# CW308T_EFR32MG21.net
KiCad netlist of a schematic drawn in Altium Designer
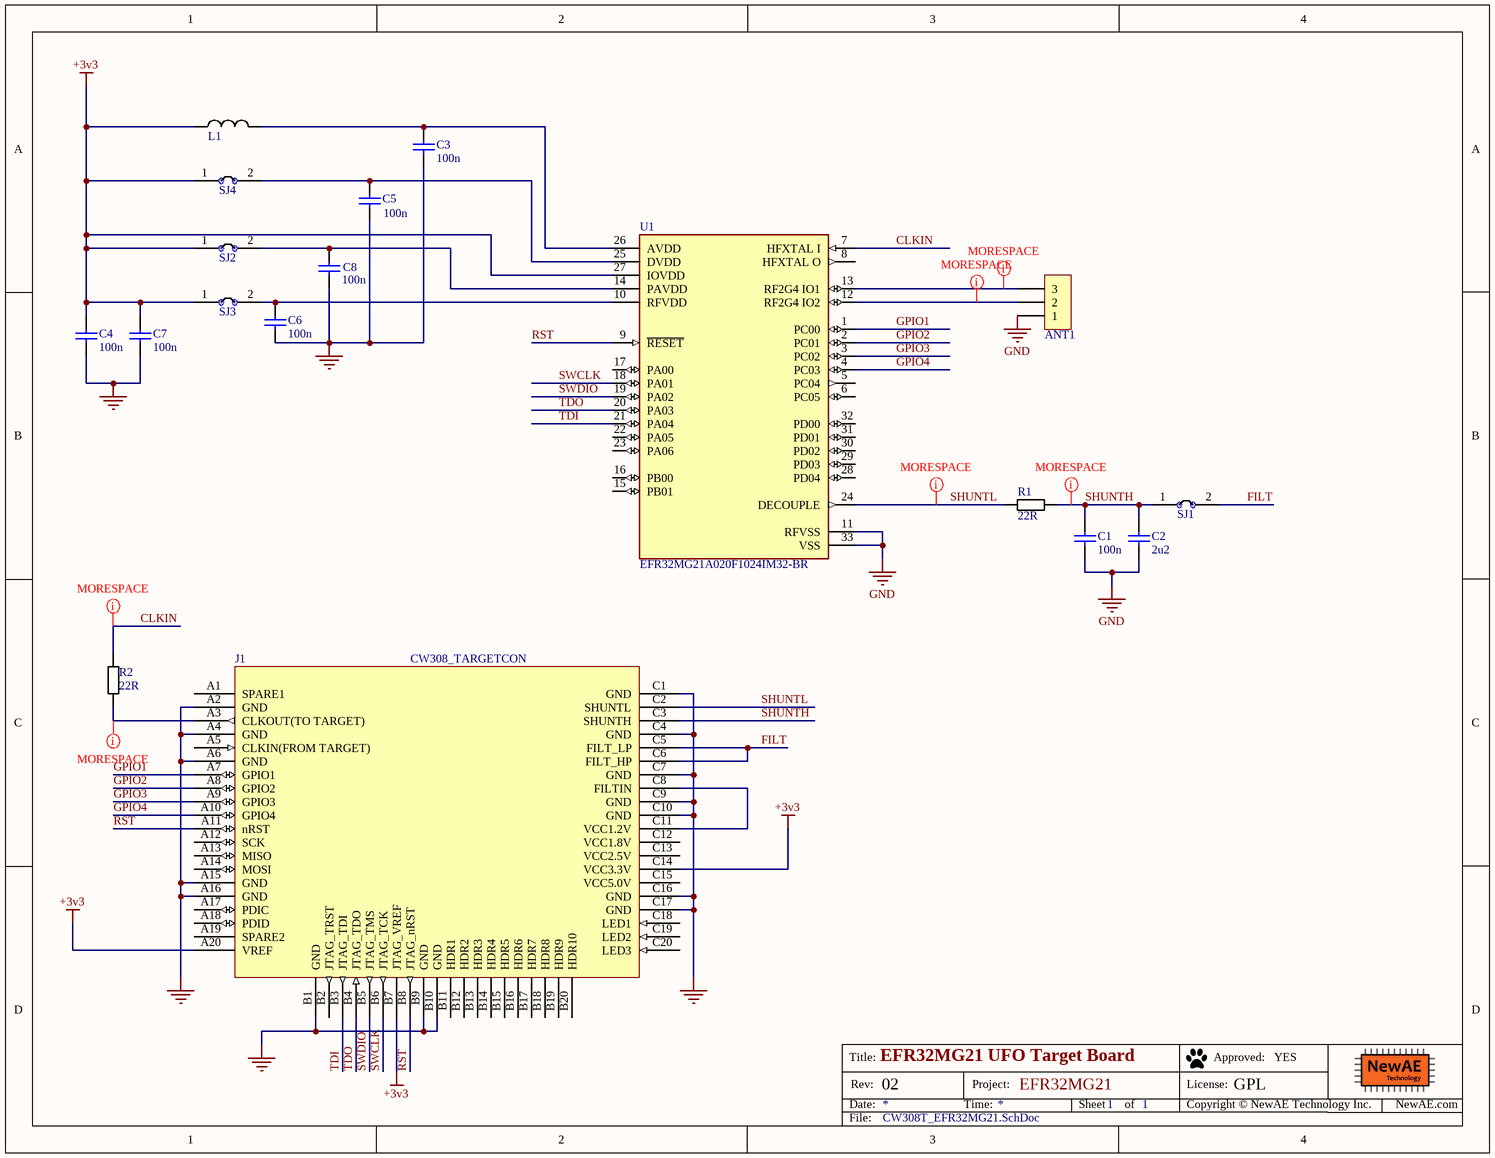
[diagram p0: CW308T_EFR32MG21.SchDoc]

(export (version "E")
  (design (tool "Eeschema 10.0.6"))
  (components
    (comp (ref "ANT1")
      (value "Straight Header Pins")
      (footprint "1x3_Straight_pins")
      (description "1x3 Straight pin header")
      (fields (field (name "PART NUMBER") "HDR_3PIN"))
      (libsource (lib "NewAE_AltiumLib") (part "1x3_Pin_Header"))
    )
    (comp (ref "C1")
      (value "100n")
      (footprint "CAPC0603_M")
      (description "100n, 0603")
      (fields (field (name "PART NUMBER") "CCHIP-100n-0603"))
      (libsource (lib "NewAE_AltiumLib") (part "CAP"))
    )
    (comp (ref "C2")
      (value "2u2")
      (footprint "CAPC0603_M")
      (description "2u2, 0603")
      (fields (field (name "PART NUMBER") "CCHIP-2u2-0603"))
      (libsource (lib "NewAE_AltiumLib") (part "CAP"))
    )
    (comp (ref "C3")
      (value "100n")
      (footprint "CAPC0603_M")
      (description "100n, 0603")
      (fields (field (name "PART NUMBER") "CCHIP-100n-0603"))
      (libsource (lib "NewAE_AltiumLib") (part "CAP"))
    )
    (comp (ref "C4")
      (value "100n")
      (footprint "CAPC0603_M")
      (description "100n, 0603")
      (fields (field (name "PART NUMBER") "CCHIP-100n-0603"))
      (libsource (lib "NewAE_AltiumLib") (part "CAP"))
    )
    (comp (ref "C5")
      (value "100n")
      (footprint "CAPC0603_M")
      (description "100n, 0603")
      (fields (field (name "PART NUMBER") "CCHIP-100n-0603"))
      (libsource (lib "NewAE_AltiumLib") (part "CAP"))
    )
    (comp (ref "C6")
      (value "100n")
      (footprint "CAPC0603_M")
      (description "100n, 0603")
      (fields (field (name "PART NUMBER") "CCHIP-100n-0603"))
      (libsource (lib "NewAE_AltiumLib") (part "CAP"))
    )
    (comp (ref "C7")
      (value "100n")
      (footprint "CAPC0603_M")
      (description "100n, 0603")
      (fields (field (name "PART NUMBER") "CCHIP-100n-0603"))
      (libsource (lib "NewAE_AltiumLib") (part "CAP"))
    )
    (comp (ref "C8")
      (value "100n")
      (footprint "CAPC0603_M")
      (description "100n, 0603")
      (fields (field (name "PART NUMBER") "CCHIP-100n-0603"))
      (libsource (lib "NewAE_AltiumLib") (part "CAP"))
    )
    (comp (ref "J1")
      (value "CW308_TARGETCON")
      (footprint "CW308_TBOARD_CONN")
      (description "CW308 \"Standard\" Target Board Connector")
      (fields (field (name "PART NUMBER") "CW308_TBOARD"))
      (libsource (lib "NewAE_AltiumLib") (part "CW308_TBOARD"))
    )
    (comp (ref "L1")
      (value "1k @ 1Mhz")
      (footprint "IND_0603")
      (description "Ferrite Beads HI CUR CHIP BD 0603 1000OHMS 25%")
      (fields (field (name "PART NUMBER") "FBCHIP-1k-0603"))
      (libsource (lib "NewAE_AltiumLib") (part "IND"))
    )
    (comp (ref "R1")
      (value "22R")
      (footprint "RESC1608X55N")
      (description "22R res, 0603, 1%, 1/10W")
      (fields (field (name "PART NUMBER") "RCHIP-22R-0603") (field (name "TOLERANCE") "1%"))
      (libsource (lib "") (part "RES-EU_1"))
    )
    (comp (ref "R2")
      (value "22R")
      (footprint "RESC1608X55N")
      (description "22R res, 0603, 1%, 1/10W")
      (fields (field (name "PART NUMBER") "RCHIP-22R-0603") (field (name "TOLERANCE") "1%"))
      (libsource (lib "NewAE_AltiumLib") (part "RES-EU"))
    )
    (comp (ref "SJ1")
      (value "NC")
      (footprint "SJ_2S_NC")
      (description "Solder Jumper, NC")
      (fields (field (name "PART NUMBER") "SJ_2S"))
      (libsource (lib "NewAE_AltiumLib") (part "SJ_2S"))
    )
    (comp (ref "SJ2")
      (value "NC")
      (footprint "SJ_2S_NC")
      (description "Solder Jumper, NC")
      (fields (field (name "PART NUMBER") "SJ_2S"))
      (libsource (lib "NewAE_AltiumLib") (part "SJ_2S"))
    )
    (comp (ref "SJ3")
      (value "NC")
      (footprint "SJ_2S_NC")
      (description "Solder Jumper, NC")
      (fields (field (name "PART NUMBER") "SJ_2S"))
      (libsource (lib "NewAE_AltiumLib") (part "SJ_2S"))
    )
    (comp (ref "SJ4")
      (value "NC")
      (footprint "SJ_2S_NC")
      (description "Solder Jumper, NC")
      (fields (field (name "PART NUMBER") "SJ_2S"))
      (libsource (lib "NewAE_AltiumLib") (part "SJ_2S"))
    )
    (comp (ref "U1")
      (value "EFR32MG21A020F1024IM32-BR")
      (footprint "FP-EFR32MG21A020F1024IM32-MFG")
      (description "IC MCU 2.4G 20DB MULTIPROTOCOL")
      (fields
        (field (name "MANUFACTURER") "Silicon Labs")
        (field (name "OCTOPART") "https://octopart.com/efr32mg21a020f1024im32-br-silicon+labs-98975230")
      )
      (libsource (lib "Altium Content Vault") (part "b191411bf8830235ba6647a90e145a1"))
    )
  )
  (nets
    (net (code "1") (name "+3v3") (class "Default")
      (node (ref "C4") (pin "1") (pinfunction "1_1") (pintype "passive"))
      (node (ref "C7") (pin "1") (pinfunction "1_1") (pintype "passive"))
      (node (ref "J1") (pin "A20") (pinfunction "VREF_A20") (pintype "tri_state"))
      (node (ref "J1") (pin "B7") (pinfunction "JTAG_VREF_B7") (pintype "tri_state"))
      (node (ref "J1") (pin "C14") (pinfunction "VCC3.3V_C14") (pintype "power_in"))
      (node (ref "L1") (pin "1") (pinfunction "1_1") (pintype "passive"))
      (node (ref "SJ2") (pin "1") (pinfunction "1_1") (pintype "passive"))
      (node (ref "SJ3") (pin "1") (pinfunction "1_1") (pintype "passive"))
      (node (ref "SJ4") (pin "1") (pinfunction "1_1") (pintype "passive"))
      (node (ref "U1") (pin "27") (pinfunction "IOVDD_27") (pintype "power_in"))
    )
    (net (code "2") (name "/CLKIN") (class "Default")
      (node (ref "R2") (pin "1") (pinfunction "1_1") (pintype "passive"))
      (node (ref "U1") (pin "7") (pinfunction "HFXTAL_I_7") (pintype "input"))
    )
    (net (code "3") (name "/FILT") (class "Default")
      (node (ref "J1") (pin "C5") (pinfunction "FILT_LP_C5") (pintype "passive"))
      (node (ref "J1") (pin "C6") (pinfunction "FILT_HP_C6") (pintype "passive"))
      (node (ref "SJ1") (pin "2") (pinfunction "2_2") (pintype "passive"))
    )
    (net (code "4") (name "/GPIO1") (class "Default")
      (node (ref "J1") (pin "A7") (pinfunction "GPIO1_A7") (pintype "bidirectional"))
      (node (ref "U1") (pin "1") (pinfunction "PC00_1") (pintype "bidirectional"))
    )
    (net (code "5") (name "/GPIO2") (class "Default")
      (node (ref "J1") (pin "A8") (pinfunction "GPIO2_A8") (pintype "bidirectional"))
      (node (ref "U1") (pin "2") (pinfunction "PC01_2") (pintype "bidirectional"))
    )
    (net (code "6") (name "/GPIO3") (class "Default")
      (node (ref "J1") (pin "A9") (pinfunction "GPIO3_A9") (pintype "bidirectional"))
      (node (ref "U1") (pin "3") (pinfunction "PC02_3") (pintype "bidirectional"))
    )
    (net (code "7") (name "/GPIO4") (class "Default")
      (node (ref "J1") (pin "A10") (pinfunction "GPIO4_A10") (pintype "bidirectional"))
      (node (ref "U1") (pin "4") (pinfunction "PC03_4") (pintype "bidirectional"))
    )
    (net (code "8") (name "/RST") (class "Default")
      (node (ref "J1") (pin "A11") (pinfunction "nRST_A11") (pintype "bidirectional"))
      (node (ref "J1") (pin "B8") (pinfunction "JTAG_nRST_B8") (pintype "output"))
      (node (ref "U1") (pin "9") (pinfunction "~{RESET}_9") (pintype "input"))
    )
    (net (code "9") (name "/SHUNTH") (class "Default")
      (node (ref "C1") (pin "1") (pinfunction "1_1") (pintype "passive"))
      (node (ref "C2") (pin "1") (pinfunction "1_1") (pintype "passive"))
      (node (ref "J1") (pin "C3") (pinfunction "SHUNTH_C3") (pintype "passive"))
      (node (ref "R1") (pin "2") (pinfunction "2_2") (pintype "passive"))
      (node (ref "SJ1") (pin "1") (pinfunction "1_1") (pintype "passive"))
    )
    (net (code "10") (name "/SHUNTL") (class "Default")
      (node (ref "J1") (pin "C2") (pinfunction "SHUNTL_C2") (pintype "passive"))
      (node (ref "R1") (pin "1") (pinfunction "1_1") (pintype "passive"))
      (node (ref "U1") (pin "24") (pinfunction "DECOUPLE_24") (pintype "output"))
    )
    (net (code "11") (name "/SWCLK") (class "Default")
      (node (ref "J1") (pin "B6") (pinfunction "JTAG_TCK_B6") (pintype "output"))
      (node (ref "U1") (pin "18") (pinfunction "PA01_18") (pintype "bidirectional"))
    )
    (net (code "12") (name "/SWDIO") (class "Default")
      (node (ref "J1") (pin "B5") (pinfunction "JTAG_TMS_B5") (pintype "output"))
      (node (ref "U1") (pin "19") (pinfunction "PA02_19") (pintype "bidirectional"))
    )
    (net (code "13") (name "/TDI") (class "Default")
      (node (ref "J1") (pin "B3") (pinfunction "JTAG_TDI_B3") (pintype "output"))
      (node (ref "U1") (pin "21") (pinfunction "PA04_21") (pintype "bidirectional"))
    )
    (net (code "14") (name "/TDO") (class "Default")
      (node (ref "J1") (pin "B4") (pinfunction "JTAG_TDO_B4") (pintype "input"))
      (node (ref "U1") (pin "20") (pinfunction "PA03_20") (pintype "bidirectional"))
    )
    (net (code "15") (name "GND") (class "Default")
      (node (ref "ANT1") (pin "1") (pinfunction "1_1") (pintype "passive"))
      (node (ref "C1") (pin "2") (pinfunction "2_2") (pintype "passive"))
      (node (ref "C2") (pin "2") (pinfunction "2_2") (pintype "passive"))
      (node (ref "C3") (pin "2") (pinfunction "2_2") (pintype "passive"))
      (node (ref "C4") (pin "2") (pinfunction "2_2") (pintype "passive"))
      (node (ref "C5") (pin "2") (pinfunction "2_2") (pintype "passive"))
      (node (ref "C6") (pin "2") (pinfunction "2_2") (pintype "passive"))
      (node (ref "C7") (pin "2") (pinfunction "2_2") (pintype "passive"))
      (node (ref "C8") (pin "2") (pinfunction "2_2") (pintype "passive"))
      (node (ref "J1") (pin "A15") (pinfunction "GND_A15") (pintype "passive"))
      (node (ref "J1") (pin "A16") (pinfunction "GND_A16") (pintype "passive"))
      (node (ref "J1") (pin "A2") (pinfunction "GND_A2") (pintype "passive"))
      (node (ref "J1") (pin "A4") (pinfunction "GND_A4") (pintype "passive"))
      (node (ref "J1") (pin "A6") (pinfunction "GND_A6") (pintype "power_in"))
      (node (ref "J1") (pin "B1") (pinfunction "GND_B1") (pintype "passive"))
      (node (ref "J1") (pin "B10") (pinfunction "GND_B10") (pintype "passive"))
      (node (ref "J1") (pin "B9") (pinfunction "GND_B9") (pintype "passive"))
      (node (ref "J1") (pin "C1") (pinfunction "GND_C1") (pintype "power_in"))
      (node (ref "J1") (pin "C10") (pinfunction "GND_C10") (pintype "power_in"))
      (node (ref "J1") (pin "C16") (pinfunction "GND_C16") (pintype "power_in"))
      (node (ref "J1") (pin "C17") (pinfunction "GND_C17") (pintype "power_in"))
      (node (ref "J1") (pin "C4") (pinfunction "GND_C4") (pintype "power_in"))
      (node (ref "J1") (pin "C7") (pinfunction "GND_C7") (pintype "power_in"))
      (node (ref "J1") (pin "C9") (pinfunction "GND_C9") (pintype "power_in"))
      (node (ref "U1") (pin "11") (pinfunction "RFVSS_11") (pintype "power_in"))
      (node (ref "U1") (pin "33") (pinfunction "VSS_33") (pintype "power_in"))
    )
    (net (code "16") (name "Net-(J1-CLKOUT(TO_TARGET))") (class "Default")
      (node (ref "J1") (pin "A3") (pinfunction "CLKOUT(TO_TARGET)_A3") (pintype "output"))
      (node (ref "R2") (pin "2") (pinfunction "2_2") (pintype "passive"))
    )
    (net (code "17") (name "Net-(J1-FILTIN)") (class "Default")
      (node (ref "J1") (pin "C11") (pinfunction "VCC1.2V_C11") (pintype "power_in"))
      (node (ref "J1") (pin "C8") (pinfunction "FILTIN_C8") (pintype "passive"))
    )
    (net (code "18") (name "Net-(U1-AVDD)") (class "Default")
      (node (ref "C3") (pin "1") (pinfunction "1_1") (pintype "passive"))
      (node (ref "L1") (pin "2") (pinfunction "2_2") (pintype "passive"))
      (node (ref "U1") (pin "26") (pinfunction "AVDD_26") (pintype "power_in"))
    )
    (net (code "19") (name "Net-(U1-DVDD)") (class "Default")
      (node (ref "C5") (pin "1") (pinfunction "1_1") (pintype "passive"))
      (node (ref "SJ4") (pin "2") (pinfunction "2_2") (pintype "passive"))
      (node (ref "U1") (pin "25") (pinfunction "DVDD_25") (pintype "power_in"))
    )
    (net (code "20") (name "Net-(U1-PAVDD)") (class "Default")
      (node (ref "C8") (pin "1") (pinfunction "1_1") (pintype "passive"))
      (node (ref "SJ2") (pin "2") (pinfunction "2_2") (pintype "passive"))
      (node (ref "U1") (pin "14") (pinfunction "PAVDD_14") (pintype "power_in"))
    )
    (net (code "21") (name "Net-(U1-RF2G4_IO1)") (class "Default")
      (node (ref "ANT1") (pin "3") (pinfunction "3_3") (pintype "passive"))
      (node (ref "U1") (pin "13") (pinfunction "RF2G4_IO1_13") (pintype "bidirectional"))
    )
    (net (code "22") (name "Net-(U1-RF2G4_IO2)") (class "Default")
      (node (ref "ANT1") (pin "2") (pinfunction "2_2") (pintype "passive"))
      (node (ref "U1") (pin "12") (pinfunction "RF2G4_IO2_12") (pintype "bidirectional"))
    )
    (net (code "23") (name "Net-(U1-RFVDD)") (class "Default")
      (node (ref "C6") (pin "1") (pinfunction "1_1") (pintype "passive"))
      (node (ref "SJ3") (pin "2") (pinfunction "2_2") (pintype "passive"))
      (node (ref "U1") (pin "10") (pinfunction "RFVDD_10") (pintype "power_in"))
    )
    (net (code "24") (name "unconnected-(J1-CLKIN(FROM_TARGET)-PadA5)") (class "Default")
      (node (ref "J1") (pin "A5") (pinfunction "CLKIN(FROM_TARGET)_A5") (pintype "input"))
    )
    (net (code "25") (name "unconnected-(J1-HDR1-PadB11)") (class "Default")
      (node (ref "J1") (pin "B11") (pinfunction "HDR1_B11") (pintype "passive"))
    )
    (net (code "26") (name "unconnected-(J1-HDR2-PadB12)") (class "Default")
      (node (ref "J1") (pin "B12") (pinfunction "HDR2_B12") (pintype "passive"))
    )
    (net (code "27") (name "unconnected-(J1-HDR3-PadB13)") (class "Default")
      (node (ref "J1") (pin "B13") (pinfunction "HDR3_B13") (pintype "passive"))
    )
    (net (code "28") (name "unconnected-(J1-HDR4-PadB14)") (class "Default")
      (node (ref "J1") (pin "B14") (pinfunction "HDR4_B14") (pintype "passive"))
    )
    (net (code "29") (name "unconnected-(J1-HDR5-PadB15)") (class "Default")
      (node (ref "J1") (pin "B15") (pinfunction "HDR5_B15") (pintype "passive"))
    )
    (net (code "30") (name "unconnected-(J1-HDR6-PadB16)") (class "Default")
      (node (ref "J1") (pin "B16") (pinfunction "HDR6_B16") (pintype "passive"))
    )
    (net (code "31") (name "unconnected-(J1-HDR7-PadB17)") (class "Default")
      (node (ref "J1") (pin "B17") (pinfunction "HDR7_B17") (pintype "passive"))
    )
    (net (code "32") (name "unconnected-(J1-HDR8-PadB18)") (class "Default")
      (node (ref "J1") (pin "B18") (pinfunction "HDR8_B18") (pintype "passive"))
    )
    (net (code "33") (name "unconnected-(J1-HDR9-PadB19)") (class "Default")
      (node (ref "J1") (pin "B19") (pinfunction "HDR9_B19") (pintype "passive"))
    )
    (net (code "34") (name "unconnected-(J1-HDR10-PadB20)") (class "Default")
      (node (ref "J1") (pin "B20") (pinfunction "HDR10_B20") (pintype "passive"))
    )
    (net (code "35") (name "unconnected-(J1-JTAG_TRST-PadB2)") (class "Default")
      (node (ref "J1") (pin "B2") (pinfunction "JTAG_TRST_B2") (pintype "output"))
    )
    (net (code "36") (name "unconnected-(J1-LED1-PadC18)") (class "Default")
      (node (ref "J1") (pin "C18") (pinfunction "LED1_C18") (pintype "input"))
    )
    (net (code "37") (name "unconnected-(J1-LED2-PadC19)") (class "Default")
      (node (ref "J1") (pin "C19") (pinfunction "LED2_C19") (pintype "input"))
    )
    (net (code "38") (name "unconnected-(J1-LED3-PadC20)") (class "Default")
      (node (ref "J1") (pin "C20") (pinfunction "LED3_C20") (pintype "input"))
    )
    (net (code "39") (name "unconnected-(J1-MISO-PadA13)") (class "Default")
      (node (ref "J1") (pin "A13") (pinfunction "MISO_A13") (pintype "bidirectional"))
    )
    (net (code "40") (name "unconnected-(J1-MOSI-PadA14)") (class "Default")
      (node (ref "J1") (pin "A14") (pinfunction "MOSI_A14") (pintype "bidirectional"))
    )
    (net (code "41") (name "unconnected-(J1-PDIC-PadA17)") (class "Default")
      (node (ref "J1") (pin "A17") (pinfunction "PDIC_A17") (pintype "bidirectional"))
    )
    (net (code "42") (name "unconnected-(J1-PDID-PadA18)") (class "Default")
      (node (ref "J1") (pin "A18") (pinfunction "PDID_A18") (pintype "bidirectional"))
    )
    (net (code "43") (name "unconnected-(J1-SCK-PadA12)") (class "Default")
      (node (ref "J1") (pin "A12") (pinfunction "SCK_A12") (pintype "bidirectional"))
    )
    (net (code "44") (name "unconnected-(J1-SPARE1-PadA1)") (class "Default")
      (node (ref "J1") (pin "A1") (pinfunction "SPARE1_A1") (pintype "passive"))
    )
    (net (code "45") (name "unconnected-(J1-SPARE2-PadA19)") (class "Default")
      (node (ref "J1") (pin "A19") (pinfunction "SPARE2_A19") (pintype "passive"))
    )
    (net (code "46") (name "unconnected-(J1-VCC1.8V-PadC12)") (class "Default")
      (node (ref "J1") (pin "C12") (pinfunction "VCC1.8V_C12") (pintype "power_in"))
    )
    (net (code "47") (name "unconnected-(J1-VCC2.5V-PadC13)") (class "Default")
      (node (ref "J1") (pin "C13") (pinfunction "VCC2.5V_C13") (pintype "power_in"))
    )
    (net (code "48") (name "unconnected-(J1-VCC5.0V-PadC15)") (class "Default")
      (node (ref "J1") (pin "C15") (pinfunction "VCC5.0V_C15") (pintype "power_in"))
    )
    (net (code "49") (name "unconnected-(U1-HFXTAL_O-Pad8)") (class "Default")
      (node (ref "U1") (pin "8") (pinfunction "HFXTAL_O_8") (pintype "output"))
    )
    (net (code "50") (name "unconnected-(U1-PA00-Pad17)") (class "Default")
      (node (ref "U1") (pin "17") (pinfunction "PA00_17") (pintype "bidirectional"))
    )
    (net (code "51") (name "unconnected-(U1-PA05-Pad22)") (class "Default")
      (node (ref "U1") (pin "22") (pinfunction "PA05_22") (pintype "bidirectional"))
    )
    (net (code "52") (name "unconnected-(U1-PA06-Pad23)") (class "Default")
      (node (ref "U1") (pin "23") (pinfunction "PA06_23") (pintype "bidirectional"))
    )
    (net (code "53") (name "unconnected-(U1-PB00-Pad16)") (class "Default")
      (node (ref "U1") (pin "16") (pinfunction "PB00_16") (pintype "bidirectional"))
    )
    (net (code "54") (name "unconnected-(U1-PB01-Pad15)") (class "Default")
      (node (ref "U1") (pin "15") (pinfunction "PB01_15") (pintype "bidirectional"))
    )
    (net (code "55") (name "unconnected-(U1-PC04-Pad5)") (class "Default")
      (node (ref "U1") (pin "5") (pinfunction "PC04_5") (pintype "output"))
    )
    (net (code "56") (name "unconnected-(U1-PC05-Pad6)") (class "Default")
      (node (ref "U1") (pin "6") (pinfunction "PC05_6") (pintype "bidirectional"))
    )
    (net (code "57") (name "unconnected-(U1-PD00-Pad32)") (class "Default")
      (node (ref "U1") (pin "32") (pinfunction "PD00_32") (pintype "bidirectional"))
    )
    (net (code "58") (name "unconnected-(U1-PD01-Pad31)") (class "Default")
      (node (ref "U1") (pin "31") (pinfunction "PD01_31") (pintype "bidirectional"))
    )
    (net (code "59") (name "unconnected-(U1-PD02-Pad30)") (class "Default")
      (node (ref "U1") (pin "30") (pinfunction "PD02_30") (pintype "bidirectional"))
    )
    (net (code "60") (name "unconnected-(U1-PD03-Pad29)") (class "Default")
      (node (ref "U1") (pin "29") (pinfunction "PD03_29") (pintype "bidirectional"))
    )
    (net (code "61") (name "unconnected-(U1-PD04-Pad28)") (class "Default")
      (node (ref "U1") (pin "28") (pinfunction "PD04_28") (pintype "bidirectional"))
    )
  )
)
